# Ports.net
KiCad netlist of a schematic drawn in Altium Designer
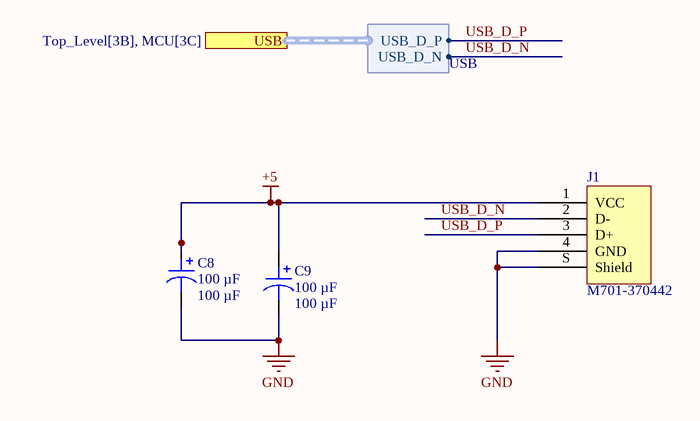
[diagram p0: Ports.SchDoc]

(export (version "E")
  (design (tool "Eeschema 10.0.6"))
  (components
    (comp (ref "C8")
      (value "100 µF")
      (footprint "CAP POL 2917_7343")
      (description "CAP TANT 100UF 10% 20V 2917")
      (fields (field (name "PART NUMBER") "T491X107K020AT") (field (name "ALTIUM_VALUE") "100 µF"))
      (libsource (lib "Celestial Altium Library - altium_library") (part "Polarised Capacitor"))
    )
    (comp (ref "C9")
      (value "100 µF")
      (footprint "CAP POL 2917_7343")
      (description "CAP TANT 100UF 10% 20V 2917")
      (fields (field (name "PART NUMBER") "T491X107K020AT") (field (name "ALTIUM_VALUE") "100 µF"))
      (libsource (lib "Celestial Altium Library - altium_library") (part "Polarised Capacitor"))
    )
    (comp (ref "J1")
      (value "M701-370442")
      (footprint "HARWIN USB M701-370442")
      (description "CONN RCPT USB2.0 TYPEB 4P SMD RA")
      (libsource (lib "Celestial Altium Library - altium_library") (part "USB 2.0 Type B"))
    )
  )
  (nets
    (net (code "2") (name "+5") (class "Default")
      (node (ref "C8") (pin "1") (pinfunction "1_1") (pintype "passive"))
      (node (ref "C9") (pin "1") (pinfunction "1_1") (pintype "passive"))
      (node (ref "J1") (pin "1") (pinfunction "VCC_1") (pintype "passive"))
    )
    (net (code "3") (name "/USB_D_N") (class "Default")
      (node (ref "J1") (pin "2") (pinfunction "D-_2") (pintype "passive"))
    )
    (net (code "4") (name "/USB_D_P") (class "Default")
      (node (ref "J1") (pin "3") (pinfunction "D+_3") (pintype "passive"))
    )
    (net (code "6") (name "GND") (class "Default")
      (node (ref "C8") (pin "2") (pinfunction "2_2") (pintype "passive"))
      (node (ref "C9") (pin "2") (pinfunction "2_2") (pintype "passive"))
      (node (ref "J1") (pin "4") (pinfunction "GND_4") (pintype "passive"))
      (node (ref "J1") (pin "S") (pinfunction "Shield_S") (pintype "passive"))
    )
  )
)
